# ISL6236_demo.net
KiCad netlist of a schematic drawn in Altium Designer
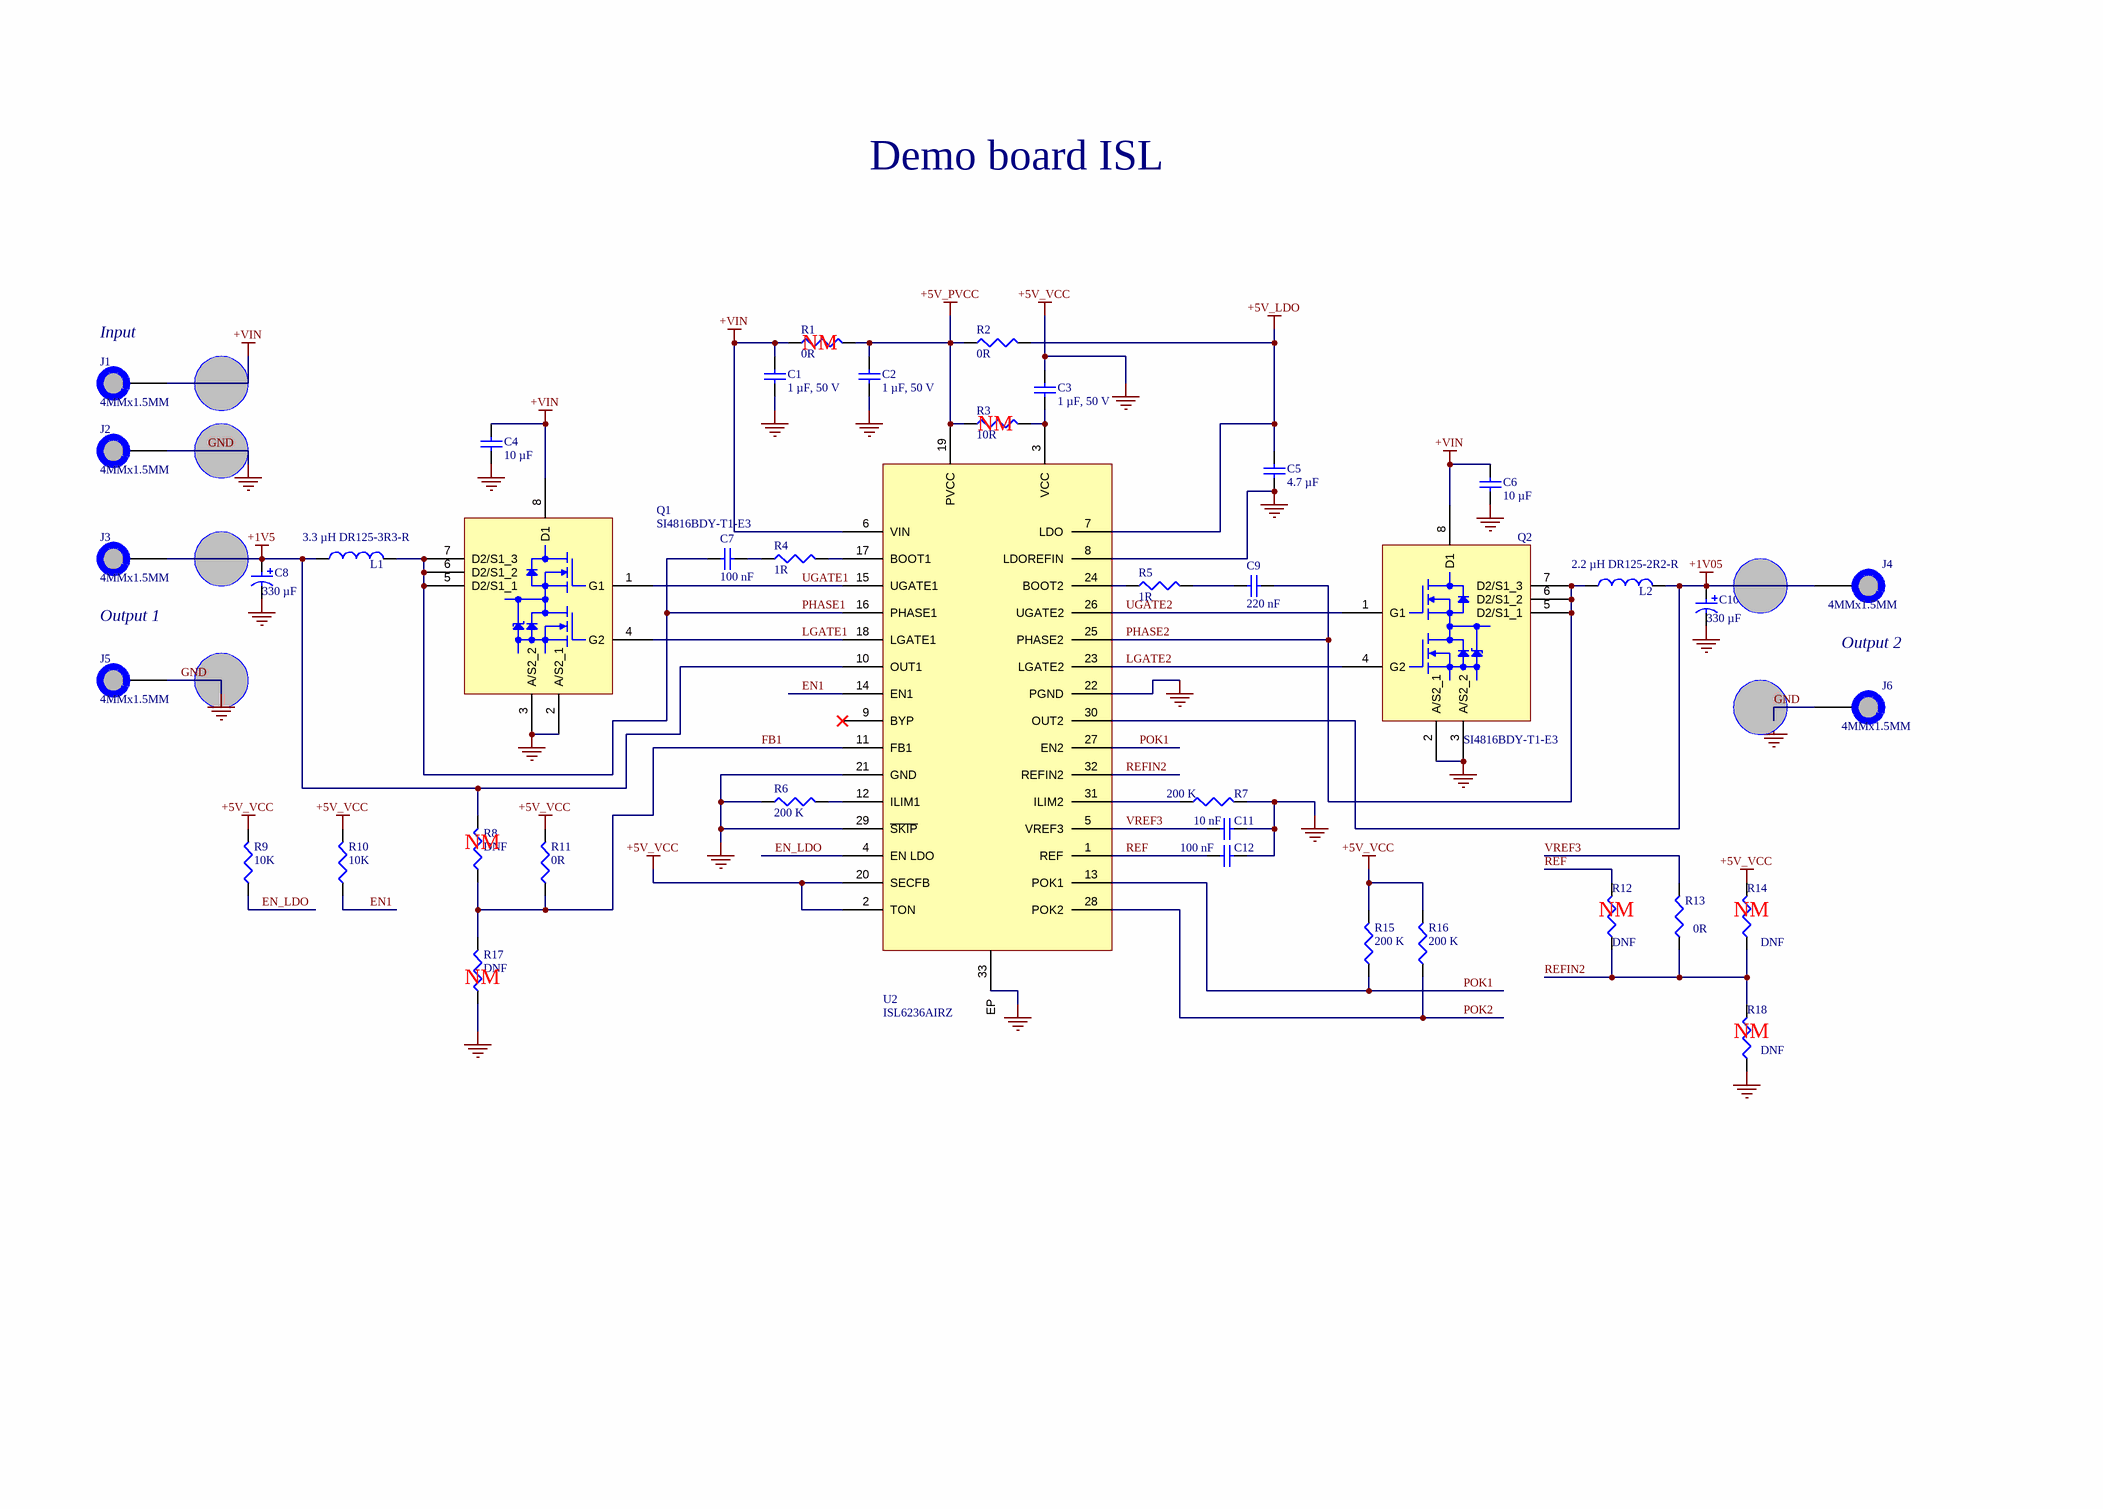
[diagram p0: ISL6236_demo.SchDoc]

(export (version "E")
  (design (tool "Eeschema 10.0.6"))
  (components
    (comp (ref "C1")
      (value "1 µF, 50 V")
      (footprint "C0805")
      (description "Multilayer Ceramic Capacitor, 1 uF, 50 V, ± 10%, X7R, 0805 [2012 Metric]")
      (fields
        (field (name "MANUFACTURER") "KEMET")
        (field (name "MANUFACTURER PART NUMBER") "C0805C105K5RACTU")
      )
      (libsource (lib "ISL6236_lib") (part "C0805C105K5RACTU"))
    )
    (comp (ref "C2")
      (value "1 µF, 50 V")
      (footprint "C0805")
      (description "Multilayer Ceramic Capacitor, 1 uF, 50 V, ± 10%, X7R, 0805 [2012 Metric]")
      (fields
        (field (name "MANUFACTURER") "KEMET")
        (field (name "MANUFACTURER PART NUMBER") "C0805C105K5RACTU")
      )
      (libsource (lib "ISL6236_lib") (part "C0805C105K5RACTU"))
    )
    (comp (ref "C3")
      (value "1 µF, 50 V")
      (footprint "C0805")
      (description "Multilayer Ceramic Capacitor, 1 uF, 50 V, ± 10%, X7R, 0805 [2012 Metric]")
      (fields
        (field (name "MANUFACTURER") "KEMET")
        (field (name "MANUFACTURER PART NUMBER") "C0805C105K5RACTU")
      )
      (libsource (lib "ISL6236_lib") (part "C0805C105K5RACTU"))
    )
    (comp (ref "C4")
      (value "10 µF")
      (footprint "C1210")
      (description "Multilayer Ceramic Capacitor, 10 uF, 35 V, ± 10%, X5R, 1210 [3225 Metric]")
      (fields
        (field (name "MANUFACTURER") "KEMET")
        (field (name "MANUFACTURER PART NUMBER") "C1210C106K6PACTU")
      )
      (libsource (lib "ISL6236_lib") (part "C1210C106K6PACTU"))
    )
    (comp (ref "C5")
      (value "4.7 µF")
      (footprint "C1206")
      (description "C Series 1206 4.7 uF 50 V ±10 % Tolerance X5R SMT Multilayer Ceramic Capacitor")
      (fields
        (field (name "MANUFACTURER") "TDK")
        (field (name "MANUFACTURER PART NUMBER") "C3216X5R1H475K160AB")
      )
      (libsource (lib "ISL6236_lib") (part "C3216X5R1H475K160AB"))
    )
    (comp (ref "C6")
      (value "10 µF")
      (footprint "C1210")
      (description "Multilayer Ceramic Capacitor, 10 uF, 35 V, ± 10%, X5R, 1210 [3225 Metric]")
      (fields
        (field (name "MANUFACTURER") "KEMET")
        (field (name "MANUFACTURER PART NUMBER") "C1210C106K6PACTU")
      )
      (libsource (lib "ISL6236_lib") (part "C1210C106K6PACTU"))
    )
    (comp (ref "C7")
      (value "100 nF")
      (footprint "C0805")
      (description "Multilayer Ceramic Capacitor, 0.1 uF, 50 V, ± 10%, X7R, 0805 [2012 Metric]")
      (fields
        (field (name "MANUFACTURER") "KEMET")
        (field (name "MANUFACTURER PART NUMBER") "C0805C104K5RACTU")
      )
      (libsource (lib "ISL6236_lib") (part "C0805C104K5RACTU"))
    )
    (comp (ref "C8")
      (value "330 µF")
      (footprint "C1210")
      (description "Cap Tant Solid 330uF 10V X CASE 20% (7.3 X 4.3 X 4mm) SMD 7343-43 0.004 Ohm 125 C T/R")
      (fields
        (field (name "MANUFACTURER") "KEMET")
        (field (name "MANUFACTURER PART NUMBER") "T530X337M010AHE004")
      )
      (libsource (lib "ISL6236_lib") (part "T530X337M010AHE004"))
    )
    (comp (ref "C9")
      (value "220 nF")
      (footprint "C0805")
      (description "Multilayer Ceramic Capacitor, 0.22 uF, 50 V, ± 10%, X7R, 0805 [2012 Metric]")
      (fields
        (field (name "MANUFACTURER") "KEMET")
        (field (name "MANUFACTURER PART NUMBER") "C0805C224K5RACTU")
      )
      (libsource (lib "ISL6236_lib") (part "C0805C224K5RACTU"))
    )
    (comp (ref "C10")
      (value "330 µF")
      (footprint "C1210")
      (description "Cap Tant Solid 330uF 10V X CASE 20% (7.3 X 4.3 X 4mm) SMD 7343-43 0.004 Ohm 125 C T/R")
      (fields
        (field (name "MANUFACTURER") "KEMET")
        (field (name "MANUFACTURER PART NUMBER") "T530X337M010AHE004")
      )
      (libsource (lib "ISL6236_lib") (part "T530X337M010AHE004"))
    )
    (comp (ref "C11")
      (value "10 nF")
      (footprint "C0805")
      (description "0805 C 10nF Ceramic Multilayer Capacitor; 50 VDC; +125degC; X7R Dielec; +/-10%")
      (fields
        (field (name "MANUFACTURER") "KEMET")
        (field (name "MANUFACTURER PART NUMBER") "C0805F103K5RACTU")
      )
      (libsource (lib "ISL6236_lib") (part "C0805F103K5RACTU"))
    )
    (comp (ref "C12")
      (value "100 nF")
      (footprint "C0805")
      (description "Multilayer Ceramic Capacitor, 0.1 uF, 50 V, ± 10%, X7R, 0805 [2012 Metric]")
      (fields
        (field (name "MANUFACTURER") "KEMET")
        (field (name "MANUFACTURER PART NUMBER") "C0805C104K5RACTU")
      )
      (libsource (lib "ISL6236_lib") (part "C0805C104K5RACTU"))
    )
    (comp (ref "J1")
      (value "4MMx1.5MM")
      (footprint "PAD_HOLE_4MMx1MM5")
      (description "Pad with hole 4 mm x 1.5 mm")
      (libsource (lib "") (part "PAD_HOLE_4MMx1MM5_1"))
    )
    (comp (ref "J2")
      (value "4MMx1.5MM")
      (footprint "PAD_HOLE_4MMx1MM5")
      (description "Pad with hole 4 mm x 1.5 mm")
      (libsource (lib "") (part "PAD_HOLE_4MMx1MM5_1"))
    )
    (comp (ref "J3")
      (value "4MMx1.5MM")
      (footprint "PAD_HOLE_4MMx1MM5")
      (description "Pad with hole 4 mm x 1.5 mm")
      (libsource (lib "") (part "PAD_HOLE_4MMx1MM5_1"))
    )
    (comp (ref "J4")
      (value "4MMx1.5MM")
      (footprint "PAD_HOLE_4MMx1MM5")
      (description "Pad with hole 4 mm x 1.5 mm")
      (libsource (lib "ISL6236_lib") (part "PAD_HOLE_4MMx1MM5"))
    )
    (comp (ref "J5")
      (value "4MMx1.5MM")
      (footprint "PAD_HOLE_4MMx1MM5")
      (description "Pad with hole 4 mm x 1.5 mm")
      (libsource (lib "") (part "PAD_HOLE_4MMx1MM5_1"))
    )
    (comp (ref "J6")
      (value "4MMx1.5MM")
      (footprint "PAD_HOLE_4MMx1MM5")
      (description "Pad with hole 4 mm x 1.5 mm")
      (libsource (lib "ISL6236_lib") (part "PAD_HOLE_4MMx1MM5"))
    )
    (comp (ref "L1")
      (value "3.3 µH DR125-3R3-R")
      (footprint "DR125")
      (description "Inductor Power Shielded Drum Core 3.3uH 20% 100KHz Ferrite 9.26A 6.3mOhm DCR T/R")
      (fields
        (field (name "MANUFACTURER") "Eaton - Electronics Division")
        (field (name "MANUFACTURER PART NUMBER") "DR125-3R3-R")
      )
      (libsource (lib "ISL6236_lib") (part "DR125-3R3-R"))
    )
    (comp (ref "L2")
      (value "2.2 µH DR125-2R2-R")
      (footprint "DR125")
      (description "Ind Power Shielded Wirewound 2.2uH 20% 100KHz Ferrite 10.9A T/R")
      (fields
        (field (name "MANUFACTURER") "Eaton Cooper")
        (field (name "MANUFACTURER PART NUMBER") "DR125-2R2-R")
      )
      (libsource (lib "ISL6236_lib") (part "DR125-2R2-R"))
    )
    (comp (ref "Q1")
      (value "SI4816BDY-T1-E3")
      (footprint "SO-8")
      (description "Transistor MOSFET Array Dual N-CH 30V 5.8A/8.2A 8-Pin SOIC T/R")
      (fields (field (name "MANUFACTURER") "Vishay Siliconix"))
      (libsource (lib "ISL6236_lib") (part "SI4816BDY-T1-E3"))
    )
    (comp (ref "Q2")
      (value "SI4816BDY-T1-E3")
      (footprint "SO-8")
      (description "Transistor MOSFET Array Dual N-CH 30V 5.8A/8.2A 8-Pin SOIC T/R")
      (fields (field (name "MANUFACTURER") "Vishay Siliconix"))
      (libsource (lib "") (part "SI4816BDY-T1-E3_1"))
    )
    (comp (ref "R1")
      (value "0R")
      (footprint "R0805")
      (description "Zero Ohm Resistor, 0805 [2012 Metric], Thick Film, 125 mW, 2 A, Surface Mount")
      (fields
        (field (name "MANUFACTURER") "Yageo")
        (field (name "MANUFACTURER PART NUMBER") "AC0805JR-070RL")
      )
      (libsource (lib "ISL6236_lib") (part "AC0805JR-070RL"))
    )
    (comp (ref "R2")
      (value "0R")
      (footprint "R0805")
      (description "Zero Ohm Resistor, 0805 [2012 Metric], Thick Film, 125 mW, 2 A, Surface Mount")
      (fields
        (field (name "MANUFACTURER") "Yageo")
        (field (name "MANUFACTURER PART NUMBER") "AC0805JR-070RL")
      )
      (libsource (lib "ISL6236_lib") (part "AC0805JR-070RL"))
    )
    (comp (ref "R3")
      (value "10R")
      (footprint "R0805")
      (description "SMD Chip Resistor, 10 Ohm, ± 1%, 125 mW, 0805 [2012 Metric], Thick Film, General Purpose")
      (fields
        (field (name "MANUFACTURER") "Yageo")
        (field (name "MANUFACTURER PART NUMBER") "AC0805FR-0710RL")
      )
      (libsource (lib "ISL6236_lib") (part "AC0805FR-0710RL"))
    )
    (comp (ref "R4")
      (value "1R")
      (footprint "R0805")
      (description "SMD Chip Resistor, 1 Ohm, ± 1%, 125 mW, 0805 [2012 Metric], Thick Film, General Purpose")
      (fields
        (field (name "MANUFACTURER") "Yageo")
        (field (name "MANUFACTURER PART NUMBER") "AC0805FR-071RL")
      )
      (libsource (lib "ISL6236_lib") (part "AC0805FR-071RL"))
    )
    (comp (ref "R5")
      (value "1R")
      (footprint "R0805")
      (description "SMD Chip Resistor, 1 Ohm, ± 1%, 125 mW, 0805 [2012 Metric], Thick Film, General Purpose")
      (fields
        (field (name "MANUFACTURER") "Yageo")
        (field (name "MANUFACTURER PART NUMBER") "AC0805FR-071RL")
      )
      (libsource (lib "ISL6236_lib") (part "AC0805FR-071RL"))
    )
    (comp (ref "R6")
      (value "200 K")
      (footprint "R0805")
      (description "SMD Chip Resistor, 200 kOhm, ± 1%, 125 mW, 0805 [2012 Metric], Thick Film, General Purpose")
      (fields
        (field (name "MANUFACTURER") "Yageo")
        (field (name "MANUFACTURER PART NUMBER") "AC0805FR-07200KL")
      )
      (libsource (lib "ISL6236_lib") (part "AC0805FR-07200KL"))
    )
    (comp (ref "R7")
      (value "200 K")
      (footprint "R0805")
      (description "SMD Chip Resistor, 200 kOhm, ± 1%, 125 mW, 0805 [2012 Metric], Thick Film, General Purpose")
      (fields
        (field (name "MANUFACTURER") "Yageo")
        (field (name "MANUFACTURER PART NUMBER") "AC0805FR-07200KL")
      )
      (libsource (lib "ISL6236_lib") (part "AC0805FR-07200KL"))
    )
    (comp (ref "R8") (value "DNF") (footprint "R0805") (libsource (lib "ISL6236_lib") (part "RES")))
    (comp (ref "R9")
      (value "10K")
      (footprint "R0805")
      (description "SMD Chip Resistor, 10 kOhm, ± 1%, 125 mW, 0805 [2012 Metric], Thick Film, General Purpose")
      (fields
        (field (name "MANUFACTURER") "Yageo")
        (field (name "MANUFACTURER PART NUMBER") "AC0805FR-0710KL")
      )
      (libsource (lib "ISL6236_lib") (part "AC0805FR-0710KL"))
    )
    (comp (ref "R10")
      (value "10K")
      (footprint "R0805")
      (description "SMD Chip Resistor, 10 kOhm, ± 1%, 125 mW, 0805 [2012 Metric], Thick Film, General Purpose")
      (fields
        (field (name "MANUFACTURER") "Yageo")
        (field (name "MANUFACTURER PART NUMBER") "AC0805FR-0710KL")
      )
      (libsource (lib "ISL6236_lib") (part "AC0805FR-0710KL"))
    )
    (comp (ref "R11")
      (value "0R")
      (footprint "R0805")
      (description "Zero Ohm Resistor, 0805 [2012 Metric], Thick Film, 125 mW, 2 A, Surface Mount")
      (fields
        (field (name "MANUFACTURER") "Yageo")
        (field (name "MANUFACTURER PART NUMBER") "AC0805JR-070RL")
      )
      (libsource (lib "ISL6236_lib") (part "AC0805JR-070RL"))
    )
    (comp (ref "R12") (value "DNF") (footprint "R0805") (libsource (lib "ISL6236_lib") (part "RES")))
    (comp (ref "R13")
      (value "0R")
      (footprint "R0805")
      (description "Zero Ohm Resistor, 0805 [2012 Metric], Thick Film, 125 mW, 2 A, Surface Mount")
      (fields
        (field (name "MANUFACTURER") "Yageo")
        (field (name "MANUFACTURER PART NUMBER") "AC0805JR-070RL")
      )
      (libsource (lib "ISL6236_lib") (part "AC0805JR-070RL"))
    )
    (comp (ref "R14") (value "DNF") (footprint "R0805") (libsource (lib "ISL6236_lib") (part "RES")))
    (comp (ref "R15")
      (value "200 K")
      (footprint "R0805")
      (description "SMD Chip Resistor, 200 kOhm, ± 1%, 125 mW, 0805 [2012 Metric], Thick Film, General Purpose")
      (fields
        (field (name "MANUFACTURER") "Yageo")
        (field (name "MANUFACTURER PART NUMBER") "AC0805FR-07200KL")
      )
      (libsource (lib "ISL6236_lib") (part "AC0805FR-07200KL"))
    )
    (comp (ref "R16")
      (value "200 K")
      (footprint "R0805")
      (description "SMD Chip Resistor, 200 kOhm, ± 1%, 125 mW, 0805 [2012 Metric], Thick Film, General Purpose")
      (fields
        (field (name "MANUFACTURER") "Yageo")
        (field (name "MANUFACTURER PART NUMBER") "AC0805FR-07200KL")
      )
      (libsource (lib "ISL6236_lib") (part "AC0805FR-07200KL"))
    )
    (comp (ref "R17") (value "DNF") (footprint "R0805") (libsource (lib "ISL6236_lib") (part "RES")))
    (comp (ref "R18") (value "DNF") (footprint "R0805") (libsource (lib "ISL6236_lib") (part "RES")))
    (comp (ref "U2")
      (value "ISL6236AIRZ")
      (footprint "L32.5x5B")
      (description "ISL6236A Series 25 V Dual Step-Down Switch-Mode Power-Supply Controller - QFN-32")
      (fields (field (name "MANUFACTURER") "Renesas"))
      (libsource (lib "ISL6236_lib") (part "ISL6236AIRZ"))
    )
  )
  (nets
    (net (code "1") (name "+1V5") (class "Default")
      (node (ref "C8") (pin "1") (pinfunction "1_1") (pintype "passive"))
      (node (ref "J3") (pin "1") (pinfunction "1_1") (pintype "passive"))
      (node (ref "L1") (pin "1") (pinfunction "1_1") (pintype "passive"))
      (node (ref "R8") (pin "2") (pinfunction "2_2") (pintype "passive"))
      (node (ref "U2") (pin "10") (pinfunction "OUT1_10") (pintype "passive"))
    )
    (net (code "2") (name "+1V05") (class "Default")
      (node (ref "C10") (pin "1") (pinfunction "1_1") (pintype "passive"))
      (node (ref "J4") (pin "1") (pinfunction "1_1") (pintype "passive"))
      (node (ref "L2") (pin "2") (pinfunction "2_2") (pintype "passive"))
      (node (ref "U2") (pin "30") (pinfunction "OUT2_30") (pintype "passive"))
    )
    (net (code "3") (name "+5V_LDO") (class "Default")
      (node (ref "C5") (pin "2") (pinfunction "2_2") (pintype "passive"))
      (node (ref "R2") (pin "2") (pinfunction "2_2") (pintype "passive"))
      (node (ref "U2") (pin "7") (pinfunction "LDO_7") (pintype "passive"))
    )
    (net (code "4") (name "+5V_PVCC") (class "Default")
      (node (ref "C2") (pin "2") (pinfunction "2_2") (pintype "passive"))
      (node (ref "R1") (pin "2") (pinfunction "2_2") (pintype "passive"))
      (node (ref "R2") (pin "1") (pinfunction "1_1") (pintype "passive"))
      (node (ref "R3") (pin "1") (pinfunction "1_1") (pintype "passive"))
      (node (ref "U2") (pin "19") (pinfunction "PVCC_19") (pintype "passive"))
    )
    (net (code "5") (name "+5V_VCC") (class "Default")
      (node (ref "C1") (pin "1") (pinfunction "1_1") (pintype "passive"))
      (node (ref "C10") (pin "2") (pinfunction "2_2") (pintype "passive"))
      (node (ref "C11") (pin "2") (pinfunction "2_2") (pintype "passive"))
      (node (ref "C12") (pin "2") (pinfunction "2_2") (pintype "passive"))
      (node (ref "C2") (pin "1") (pinfunction "1_1") (pintype "passive"))
      (node (ref "C3") (pin "2") (pinfunction "2_2") (pintype "passive"))
      (node (ref "C4") (pin "1") (pinfunction "1_1") (pintype "passive"))
      (node (ref "C5") (pin "1") (pinfunction "1_1") (pintype "passive"))
      (node (ref "C6") (pin "1") (pinfunction "1_1") (pintype "passive"))
      (node (ref "C8") (pin "2") (pinfunction "2_2") (pintype "passive"))
      (node (ref "J2") (pin "1") (pinfunction "1_1") (pintype "passive"))
      (node (ref "J5") (pin "1") (pinfunction "1_1") (pintype "passive"))
      (node (ref "J6") (pin "1") (pinfunction "1_1") (pintype "passive"))
      (node (ref "Q1") (pin "2") (pinfunction "A/S2_1_2") (pintype "passive"))
      (node (ref "Q1") (pin "3") (pinfunction "A/S2_2_3") (pintype "passive"))
      (node (ref "Q2") (pin "2") (pinfunction "A/S2_1_2") (pintype "passive"))
      (node (ref "Q2") (pin "3") (pinfunction "A/S2_2_3") (pintype "passive"))
      (node (ref "R10") (pin "2") (pinfunction "2_2") (pintype "passive"))
      (node (ref "R11") (pin "2") (pinfunction "2_2") (pintype "passive"))
      (node (ref "R14") (pin "2") (pinfunction "2_2") (pintype "passive"))
      (node (ref "R15") (pin "2") (pinfunction "2_2") (pintype "passive"))
      (node (ref "R16") (pin "2") (pinfunction "2_2") (pintype "passive"))
      (node (ref "R17") (pin "1") (pinfunction "1_1") (pintype "passive"))
      (node (ref "R18") (pin "1") (pinfunction "1_1") (pintype "passive"))
      (node (ref "R6") (pin "1") (pinfunction "1_1") (pintype "passive"))
      (node (ref "R7") (pin "2") (pinfunction "2_2") (pintype "passive"))
      (node (ref "R9") (pin "2") (pinfunction "2_2") (pintype "passive"))
      (node (ref "U2") (pin "2") (pinfunction "TON_2") (pintype "passive"))
      (node (ref "U2") (pin "20") (pinfunction "SECFB_20") (pintype "passive"))
      (node (ref "U2") (pin "21") (pinfunction "GND_21") (pintype "passive"))
      (node (ref "U2") (pin "22") (pinfunction "PGND_22") (pintype "passive"))
      (node (ref "U2") (pin "29") (pinfunction "~{SKIP}_29") (pintype "passive"))
      (node (ref "U2") (pin "8") (pinfunction "LDOREFIN_8") (pintype "passive"))
    )
    (net (code "6") (name "+VIN") (class "Default")
      (node (ref "C1") (pin "2") (pinfunction "2_2") (pintype "passive"))
      (node (ref "C4") (pin "2") (pinfunction "2_2") (pintype "passive"))
      (node (ref "C6") (pin "2") (pinfunction "2_2") (pintype "passive"))
      (node (ref "J1") (pin "1") (pinfunction "1_1") (pintype "passive"))
      (node (ref "Q1") (pin "8") (pinfunction "D1_8") (pintype "passive"))
      (node (ref "Q2") (pin "8") (pinfunction "D1_8") (pintype "passive"))
      (node (ref "R1") (pin "1") (pinfunction "1_1") (pintype "passive"))
      (node (ref "U2") (pin "6") (pinfunction "VIN_6") (pintype "passive"))
    )
    (net (code "7") (name "/EN1") (class "Default")
      (node (ref "R10") (pin "1") (pinfunction "1_1") (pintype "passive"))
      (node (ref "U2") (pin "14") (pinfunction "EN1_14") (pintype "passive"))
    )
    (net (code "8") (name "/EN_LDO") (class "Default")
      (node (ref "R9") (pin "1") (pinfunction "1_1") (pintype "passive"))
      (node (ref "U2") (pin "4") (pinfunction "EN_LDO_4") (pintype "passive"))
    )
    (net (code "9") (name "/FB1") (class "Default")
      (node (ref "R11") (pin "1") (pinfunction "1_1") (pintype "passive"))
      (node (ref "R17") (pin "2") (pinfunction "2_2") (pintype "passive"))
      (node (ref "R8") (pin "1") (pinfunction "1_1") (pintype "passive"))
      (node (ref "U2") (pin "11") (pinfunction "FB1_11") (pintype "passive"))
    )
    (net (code "10") (name "/LGATE1") (class "Default")
      (node (ref "Q1") (pin "4") (pinfunction "G2_4") (pintype "passive"))
      (node (ref "U2") (pin "18") (pinfunction "LGATE1_18") (pintype "passive"))
    )
    (net (code "11") (name "/LGATE2") (class "Default")
      (node (ref "Q2") (pin "4") (pinfunction "G2_4") (pintype "passive"))
      (node (ref "U2") (pin "23") (pinfunction "LGATE2_23") (pintype "passive"))
    )
    (net (code "12") (name "/PHASE1") (class "Default")
      (node (ref "C7") (pin "1") (pinfunction "1_1") (pintype "passive"))
      (node (ref "L1") (pin "2") (pinfunction "2_2") (pintype "passive"))
      (node (ref "Q1") (pin "5") (pinfunction "D2/S1_1_5") (pintype "passive"))
      (node (ref "Q1") (pin "6") (pinfunction "D2/S1_2_6") (pintype "passive"))
      (node (ref "Q1") (pin "7") (pinfunction "D2/S1_3_7") (pintype "passive"))
      (node (ref "U2") (pin "16") (pinfunction "PHASE1_16") (pintype "passive"))
    )
    (net (code "13") (name "/PHASE2") (class "Default")
      (node (ref "C9") (pin "1") (pinfunction "1_1") (pintype "passive"))
      (node (ref "L2") (pin "1") (pinfunction "1_1") (pintype "passive"))
      (node (ref "Q2") (pin "5") (pinfunction "D2/S1_1_5") (pintype "passive"))
      (node (ref "Q2") (pin "6") (pinfunction "D2/S1_2_6") (pintype "passive"))
      (node (ref "Q2") (pin "7") (pinfunction "D2/S1_3_7") (pintype "passive"))
      (node (ref "U2") (pin "25") (pinfunction "PHASE2_25") (pintype "passive"))
    )
    (net (code "14") (name "/POK1") (class "Default")
      (node (ref "R15") (pin "1") (pinfunction "1_1") (pintype "passive"))
      (node (ref "U2") (pin "13") (pinfunction "POK1_13") (pintype "passive"))
      (node (ref "U2") (pin "27") (pinfunction "EN2_27") (pintype "passive"))
    )
    (net (code "15") (name "/POK2") (class "Default")
      (node (ref "R16") (pin "1") (pinfunction "1_1") (pintype "passive"))
      (node (ref "U2") (pin "28") (pinfunction "POK2_28") (pintype "passive"))
    )
    (net (code "16") (name "/REF") (class "Default")
      (node (ref "C12") (pin "1") (pinfunction "1_1") (pintype "passive"))
      (node (ref "R12") (pin "2") (pinfunction "2_2") (pintype "passive"))
      (node (ref "U2") (pin "1") (pinfunction "REF_1") (pintype "passive"))
    )
    (net (code "17") (name "/REFIN2") (class "Default")
      (node (ref "R12") (pin "1") (pinfunction "1_1") (pintype "passive"))
      (node (ref "R13") (pin "1") (pinfunction "1_1") (pintype "passive"))
      (node (ref "R14") (pin "1") (pinfunction "1_1") (pintype "passive"))
      (node (ref "R18") (pin "2") (pinfunction "2_2") (pintype "passive"))
      (node (ref "U2") (pin "32") (pinfunction "REFIN2_32") (pintype "passive"))
    )
    (net (code "18") (name "/UGATE1") (class "Default")
      (node (ref "Q1") (pin "1") (pinfunction "G1_1") (pintype "passive"))
      (node (ref "U2") (pin "15") (pinfunction "UGATE1_15") (pintype "passive"))
    )
    (net (code "19") (name "/UGATE2") (class "Default")
      (node (ref "Q2") (pin "1") (pinfunction "G1_1") (pintype "passive"))
      (node (ref "U2") (pin "26") (pinfunction "UGATE2_26") (pintype "passive"))
    )
    (net (code "20") (name "/VREF3") (class "Default")
      (node (ref "C11") (pin "1") (pinfunction "1_1") (pintype "passive"))
      (node (ref "R13") (pin "2") (pinfunction "2_2") (pintype "passive"))
      (node (ref "U2") (pin "5") (pinfunction "VREF3_5") (pintype "passive"))
    )
    (net (code "21") (name "Net-(C7-Pad2)") (class "Default")
      (node (ref "C7") (pin "2") (pinfunction "2_2") (pintype "passive"))
      (node (ref "R4") (pin "1") (pinfunction "1_1") (pintype "passive"))
    )
    (net (code "22") (name "Net-(C9-Pad2)") (class "Default")
      (node (ref "C9") (pin "2") (pinfunction "2_2") (pintype "passive"))
      (node (ref "R5") (pin "2") (pinfunction "2_2") (pintype "passive"))
    )
    (net (code "23") (name "Net-(U2-BOOT1)") (class "Default")
      (node (ref "R4") (pin "2") (pinfunction "2_2") (pintype "passive"))
      (node (ref "U2") (pin "17") (pinfunction "BOOT1_17") (pintype "passive"))
    )
    (net (code "24") (name "Net-(U2-BOOT2)") (class "Default")
      (node (ref "R5") (pin "1") (pinfunction "1_1") (pintype "passive"))
      (node (ref "U2") (pin "24") (pinfunction "BOOT2_24") (pintype "passive"))
    )
    (net (code "25") (name "Net-(U2-ILIM1)") (class "Default")
      (node (ref "R6") (pin "2") (pinfunction "2_2") (pintype "passive"))
      (node (ref "U2") (pin "12") (pinfunction "ILIM1_12") (pintype "passive"))
    )
    (net (code "26") (name "Net-(U2-ILIM2)") (class "Default")
      (node (ref "R7") (pin "1") (pinfunction "1_1") (pintype "passive"))
      (node (ref "U2") (pin "31") (pinfunction "ILIM2_31") (pintype "passive"))
    )
    (net (code "27") (name "Net-(U2-VCC)") (class "Default")
      (node (ref "C3") (pin "1") (pinfunction "1_1") (pintype "passive"))
      (node (ref "R3") (pin "2") (pinfunction "2_2") (pintype "passive"))
      (node (ref "U2") (pin "3") (pinfunction "VCC_3") (pintype "passive"))
    )
    (net (code "28") (name "unconnected-(U2-BYP-Pad9)") (class "Default")
      (node (ref "U2") (pin "9") (pinfunction "BYP_9") (pintype "passive+no_connect"))
    )
    (net (code "29") (name "unconnected-(U2-EP-Pad33)") (class "Default")
      (node (ref "U2") (pin "33") (pinfunction "EP_33") (pintype "passive"))
    )
  )
)
